# LCDTFT_FPC40P_RGB_RTP.net
KiCad netlist of a schematic drawn in Altium Designer
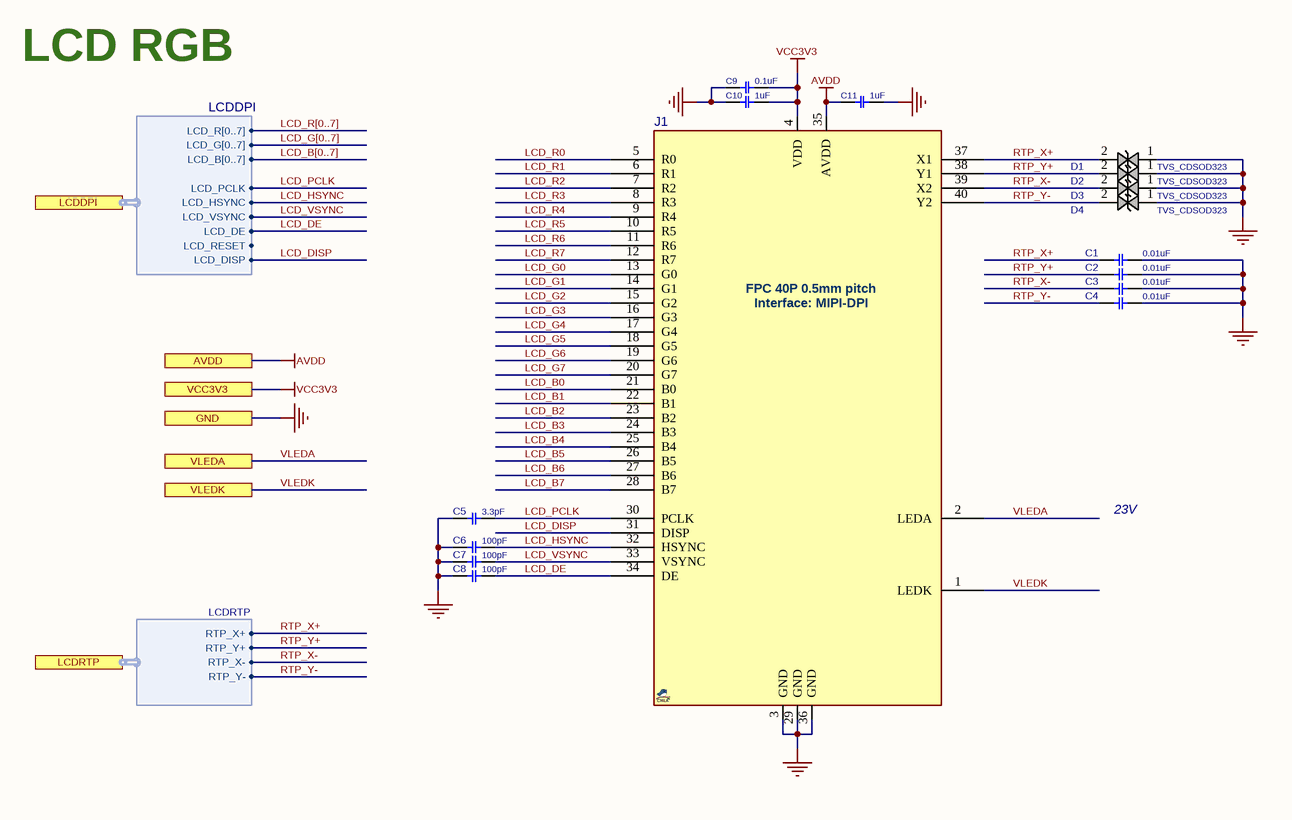
[diagram p0: LCDTFT_FPC40P_RGB_RTP.SchDoc]

(export (version "E")
  (design (tool "Eeschema 10.0.6"))
  (components
    (comp (ref "C1")
      (value "0.01uF")
      (footprint "C0402")
      (description "CAP, MLCC")
      (libsource (lib "passive_smd") (part "CAP_SMD_MLCC"))
    )
    (comp (ref "C2")
      (value "0.01uF")
      (footprint "C0402")
      (description "CAP, MLCC")
      (libsource (lib "passive_smd") (part "CAP_SMD_MLCC"))
    )
    (comp (ref "C3")
      (value "0.01uF")
      (footprint "C0402")
      (description "CAP, MLCC")
      (libsource (lib "passive_smd") (part "CAP_SMD_MLCC"))
    )
    (comp (ref "C4")
      (value "0.01uF")
      (footprint "C0402")
      (description "CAP, MLCC")
      (libsource (lib "passive_smd") (part "CAP_SMD_MLCC"))
    )
    (comp (ref "C5")
      (value "3.3pF")
      (footprint "C0402")
      (description "CAP, MLCC")
      (libsource (lib "passive_smd") (part "CAP_SMD_MLCC"))
    )
    (comp (ref "C6")
      (value "100pF")
      (footprint "C0402")
      (description "CAP, MLCC")
      (libsource (lib "passive_smd") (part "CAP_SMD_MLCC"))
    )
    (comp (ref "C7")
      (value "100pF")
      (footprint "C0402")
      (description "CAP, MLCC")
      (libsource (lib "passive_smd") (part "CAP_SMD_MLCC"))
    )
    (comp (ref "C8")
      (value "100pF")
      (footprint "C0402")
      (description "CAP, MLCC")
      (libsource (lib "passive_smd") (part "CAP_SMD_MLCC"))
    )
    (comp (ref "C9")
      (value "0.1uF")
      (footprint "C0402")
      (description "CAP, MLCC")
      (fields (field (name "MANF_P#") "GRM155R71H104KE14D") (field (name "MANF") "Murata"))
      (libsource (lib "passive_smd") (part "CAP_SMD_MLCC"))
    )
    (comp (ref "C10")
      (value "1uF")
      (footprint "C0402")
      (description "CAP, MLCC")
      (fields (field (name "MANF_P#") "CL05A105KO5NNND") (field (name "MANF") "Samsung"))
      (libsource (lib "passive_smd") (part "CAP_SMD_MLCC"))
    )
    (comp (ref "C11")
      (value "1uF")
      (footprint "C0402")
      (description "CAP, MLCC")
      (fields (field (name "MANF_P#") "CL05A105KO5NNND") (field (name "MANF") "Samsung"))
      (libsource (lib "passive_smd") (part "CAP_SMD_MLCC"))
    )
    (comp (ref "D1")
      (value "TVS_CDSOD323")
      (footprint "D0805")
      (description "TVS, ESD PROTECT, Bidirectional")
      (fields (field (name "MANF_P#") "CDSOD323-T12C") (field (name "MANF") "Bourns"))
      (libsource (lib "protect_tvs_esd_fuse") (part "TVS_CDSOD323"))
    )
    (comp (ref "D2")
      (value "TVS_CDSOD323")
      (footprint "D0805")
      (description "TVS, ESD PROTECT, Bidirectional")
      (fields (field (name "MANF_P#") "CDSOD323-T12C") (field (name "MANF") "Bourns"))
      (libsource (lib "protect_tvs_esd_fuse") (part "TVS_CDSOD323"))
    )
    (comp (ref "D3")
      (value "TVS_CDSOD323")
      (footprint "D0805")
      (description "TVS, ESD PROTECT, Bidirectional")
      (fields (field (name "MANF_P#") "CDSOD323-T12C") (field (name "MANF") "Bourns"))
      (libsource (lib "protect_tvs_esd_fuse") (part "TVS_CDSOD323"))
    )
    (comp (ref "D4")
      (value "TVS_CDSOD323")
      (footprint "D0805")
      (description "TVS, ESD PROTECT, Bidirectional")
      (fields (field (name "MANF_P#") "CDSOD323-T12C") (field (name "MANF") "Bourns"))
      (libsource (lib "protect_tvs_esd_fuse") (part "TVS_CDSOD323"))
    )
    (comp (ref "J1")
      (value "FPC_40_0.5mm")
      (footprint "FPC50_40")
      (description "LCD TFT Color, FPC40P, RGB")
      (libsource (lib "lcdtft") (part "LCDTFT_DPI_FPC40P"))
    )
  )
  (nets
    (net (code "3") (name "/LCD_B0") (class "Default")
      (node (ref "J1") (pin "21") (pinfunction "B0_21") (pintype "passive"))
    )
    (net (code "4") (name "/LCD_B1") (class "Default")
      (node (ref "J1") (pin "22") (pinfunction "B1_22") (pintype "passive"))
    )
    (net (code "5") (name "/LCD_B2") (class "Default")
      (node (ref "J1") (pin "23") (pinfunction "B2_23") (pintype "passive"))
    )
    (net (code "6") (name "/LCD_B3") (class "Default")
      (node (ref "J1") (pin "24") (pinfunction "B3_24") (pintype "passive"))
    )
    (net (code "7") (name "/LCD_B4") (class "Default")
      (node (ref "J1") (pin "25") (pinfunction "B4_25") (pintype "passive"))
    )
    (net (code "8") (name "/LCD_B5") (class "Default")
      (node (ref "J1") (pin "26") (pinfunction "B5_26") (pintype "passive"))
    )
    (net (code "9") (name "/LCD_B6") (class "Default")
      (node (ref "J1") (pin "27") (pinfunction "B6_27") (pintype "passive"))
    )
    (net (code "10") (name "/LCD_B7") (class "Default")
      (node (ref "J1") (pin "28") (pinfunction "B7_28") (pintype "passive"))
    )
    (net (code "12") (name "/LCD_DE") (class "Default")
      (node (ref "C8") (pin "1") (pinfunction "1_1") (pintype "passive"))
      (node (ref "J1") (pin "34") (pinfunction "DE_34") (pintype "passive"))
    )
    (net (code "13") (name "/LCD_DISP") (class "Default")
      (node (ref "J1") (pin "31") (pinfunction "DISP_31") (pintype "passive"))
    )
    (net (code "14") (name "/LCD_G0") (class "Default")
      (node (ref "J1") (pin "13") (pinfunction "G0_13") (pintype "passive"))
    )
    (net (code "15") (name "/LCD_G1") (class "Default")
      (node (ref "J1") (pin "14") (pinfunction "G1_14") (pintype "passive"))
    )
    (net (code "16") (name "/LCD_G2") (class "Default")
      (node (ref "J1") (pin "15") (pinfunction "G2_15") (pintype "passive"))
    )
    (net (code "17") (name "/LCD_G3") (class "Default")
      (node (ref "J1") (pin "16") (pinfunction "G3_16") (pintype "passive"))
    )
    (net (code "18") (name "/LCD_G4") (class "Default")
      (node (ref "J1") (pin "17") (pinfunction "G4_17") (pintype "passive"))
    )
    (net (code "19") (name "/LCD_G5") (class "Default")
      (node (ref "J1") (pin "18") (pinfunction "G5_18") (pintype "passive"))
    )
    (net (code "20") (name "/LCD_G6") (class "Default")
      (node (ref "J1") (pin "19") (pinfunction "G6_19") (pintype "passive"))
    )
    (net (code "21") (name "/LCD_G7") (class "Default")
      (node (ref "J1") (pin "20") (pinfunction "G7_20") (pintype "passive"))
    )
    (net (code "23") (name "/LCD_HSYNC") (class "Default")
      (node (ref "C6") (pin "1") (pinfunction "1_1") (pintype "passive"))
      (node (ref "J1") (pin "32") (pinfunction "HSYNC_32") (pintype "passive"))
    )
    (net (code "24") (name "/LCD_PCLK") (class "Default")
      (node (ref "C5") (pin "1") (pinfunction "1_1") (pintype "passive"))
      (node (ref "J1") (pin "30") (pinfunction "PCLK_30") (pintype "passive"))
    )
    (net (code "25") (name "/LCD_R0") (class "Default")
      (node (ref "J1") (pin "5") (pinfunction "R0_5") (pintype "passive"))
    )
    (net (code "26") (name "/LCD_R1") (class "Default")
      (node (ref "J1") (pin "6") (pinfunction "R1_6") (pintype "passive"))
    )
    (net (code "27") (name "/LCD_R2") (class "Default")
      (node (ref "J1") (pin "7") (pinfunction "R2_7") (pintype "passive"))
    )
    (net (code "28") (name "/LCD_R3") (class "Default")
      (node (ref "J1") (pin "8") (pinfunction "R3_8") (pintype "passive"))
    )
    (net (code "29") (name "/LCD_R4") (class "Default")
      (node (ref "J1") (pin "9") (pinfunction "R4_9") (pintype "passive"))
    )
    (net (code "30") (name "/LCD_R5") (class "Default")
      (node (ref "J1") (pin "10") (pinfunction "R5_10") (pintype "passive"))
    )
    (net (code "31") (name "/LCD_R6") (class "Default")
      (node (ref "J1") (pin "11") (pinfunction "R6_11") (pintype "passive"))
    )
    (net (code "32") (name "/LCD_R7") (class "Default")
      (node (ref "J1") (pin "12") (pinfunction "R7_12") (pintype "passive"))
    )
    (net (code "34") (name "/LCD_VSYNC") (class "Default")
      (node (ref "C7") (pin "1") (pinfunction "1_1") (pintype "passive"))
      (node (ref "J1") (pin "33") (pinfunction "VSYNC_33") (pintype "passive"))
    )
    (net (code "35") (name "/RTP_X+") (class "Default")
      (node (ref "C1") (pin "2") (pinfunction "2_2") (pintype "passive"))
      (node (ref "D1") (pin "2") (pinfunction "2_2") (pintype "passive"))
      (node (ref "J1") (pin "37") (pinfunction "X1_37") (pintype "passive"))
    )
    (net (code "36") (name "/RTP_X-") (class "Default")
      (node (ref "C3") (pin "2") (pinfunction "2_2") (pintype "passive"))
      (node (ref "D3") (pin "2") (pinfunction "2_2") (pintype "passive"))
      (node (ref "J1") (pin "39") (pinfunction "X2_39") (pintype "passive"))
    )
    (net (code "37") (name "/RTP_Y+") (class "Default")
      (node (ref "C2") (pin "2") (pinfunction "2_2") (pintype "passive"))
      (node (ref "D2") (pin "2") (pinfunction "2_2") (pintype "passive"))
      (node (ref "J1") (pin "38") (pinfunction "Y1_38") (pintype "passive"))
    )
    (net (code "38") (name "/RTP_Y-") (class "Default")
      (node (ref "C4") (pin "2") (pinfunction "2_2") (pintype "passive"))
      (node (ref "D4") (pin "2") (pinfunction "2_2") (pintype "passive"))
      (node (ref "J1") (pin "40") (pinfunction "Y2_40") (pintype "passive"))
    )
    (net (code "39") (name "/VLEDA") (class "Default")
      (node (ref "J1") (pin "2") (pinfunction "LEDA_2") (pintype "passive"))
    )
    (net (code "40") (name "/VLEDK") (class "Default")
      (node (ref "J1") (pin "1") (pinfunction "LEDK_1") (pintype "passive"))
    )
    (net (code "43") (name "AVDD") (class "Default")
      (node (ref "C11") (pin "2") (pinfunction "2_2") (pintype "passive"))
      (node (ref "J1") (pin "35") (pinfunction "AVDD_35") (pintype "passive"))
    )
    (net (code "44") (name "GND") (class "Default")
      (node (ref "C1") (pin "1") (pinfunction "1_1") (pintype "passive"))
      (node (ref "C10") (pin "2") (pinfunction "2_2") (pintype "passive"))
      (node (ref "C11") (pin "1") (pinfunction "1_1") (pintype "passive"))
      (node (ref "C2") (pin "1") (pinfunction "1_1") (pintype "passive"))
      (node (ref "C3") (pin "1") (pinfunction "1_1") (pintype "passive"))
      (node (ref "C4") (pin "1") (pinfunction "1_1") (pintype "passive"))
      (node (ref "C5") (pin "2") (pinfunction "2_2") (pintype "passive"))
      (node (ref "C6") (pin "2") (pinfunction "2_2") (pintype "passive"))
      (node (ref "C7") (pin "2") (pinfunction "2_2") (pintype "passive"))
      (node (ref "C8") (pin "2") (pinfunction "2_2") (pintype "passive"))
      (node (ref "C9") (pin "2") (pinfunction "2_2") (pintype "passive"))
      (node (ref "D1") (pin "1") (pinfunction "1_1") (pintype "passive"))
      (node (ref "D2") (pin "1") (pinfunction "1_1") (pintype "passive"))
      (node (ref "D3") (pin "1") (pinfunction "1_1") (pintype "passive"))
      (node (ref "D4") (pin "1") (pinfunction "1_1") (pintype "passive"))
      (node (ref "J1") (pin "29") (pinfunction "GND_29") (pintype "passive"))
      (node (ref "J1") (pin "3") (pinfunction "GND_3") (pintype "passive"))
      (node (ref "J1") (pin "36") (pinfunction "GND_36") (pintype "passive"))
    )
    (net (code "45") (name "VCC3V3") (class "Default")
      (node (ref "C10") (pin "1") (pinfunction "1_1") (pintype "passive"))
      (node (ref "C9") (pin "1") (pinfunction "1_1") (pintype "passive"))
      (node (ref "J1") (pin "4") (pinfunction "VDD_4") (pintype "passive"))
    )
  )
)
